# Acoustics_Board_Pg_2.net
KiCad netlist of a schematic drawn in Altium Designer
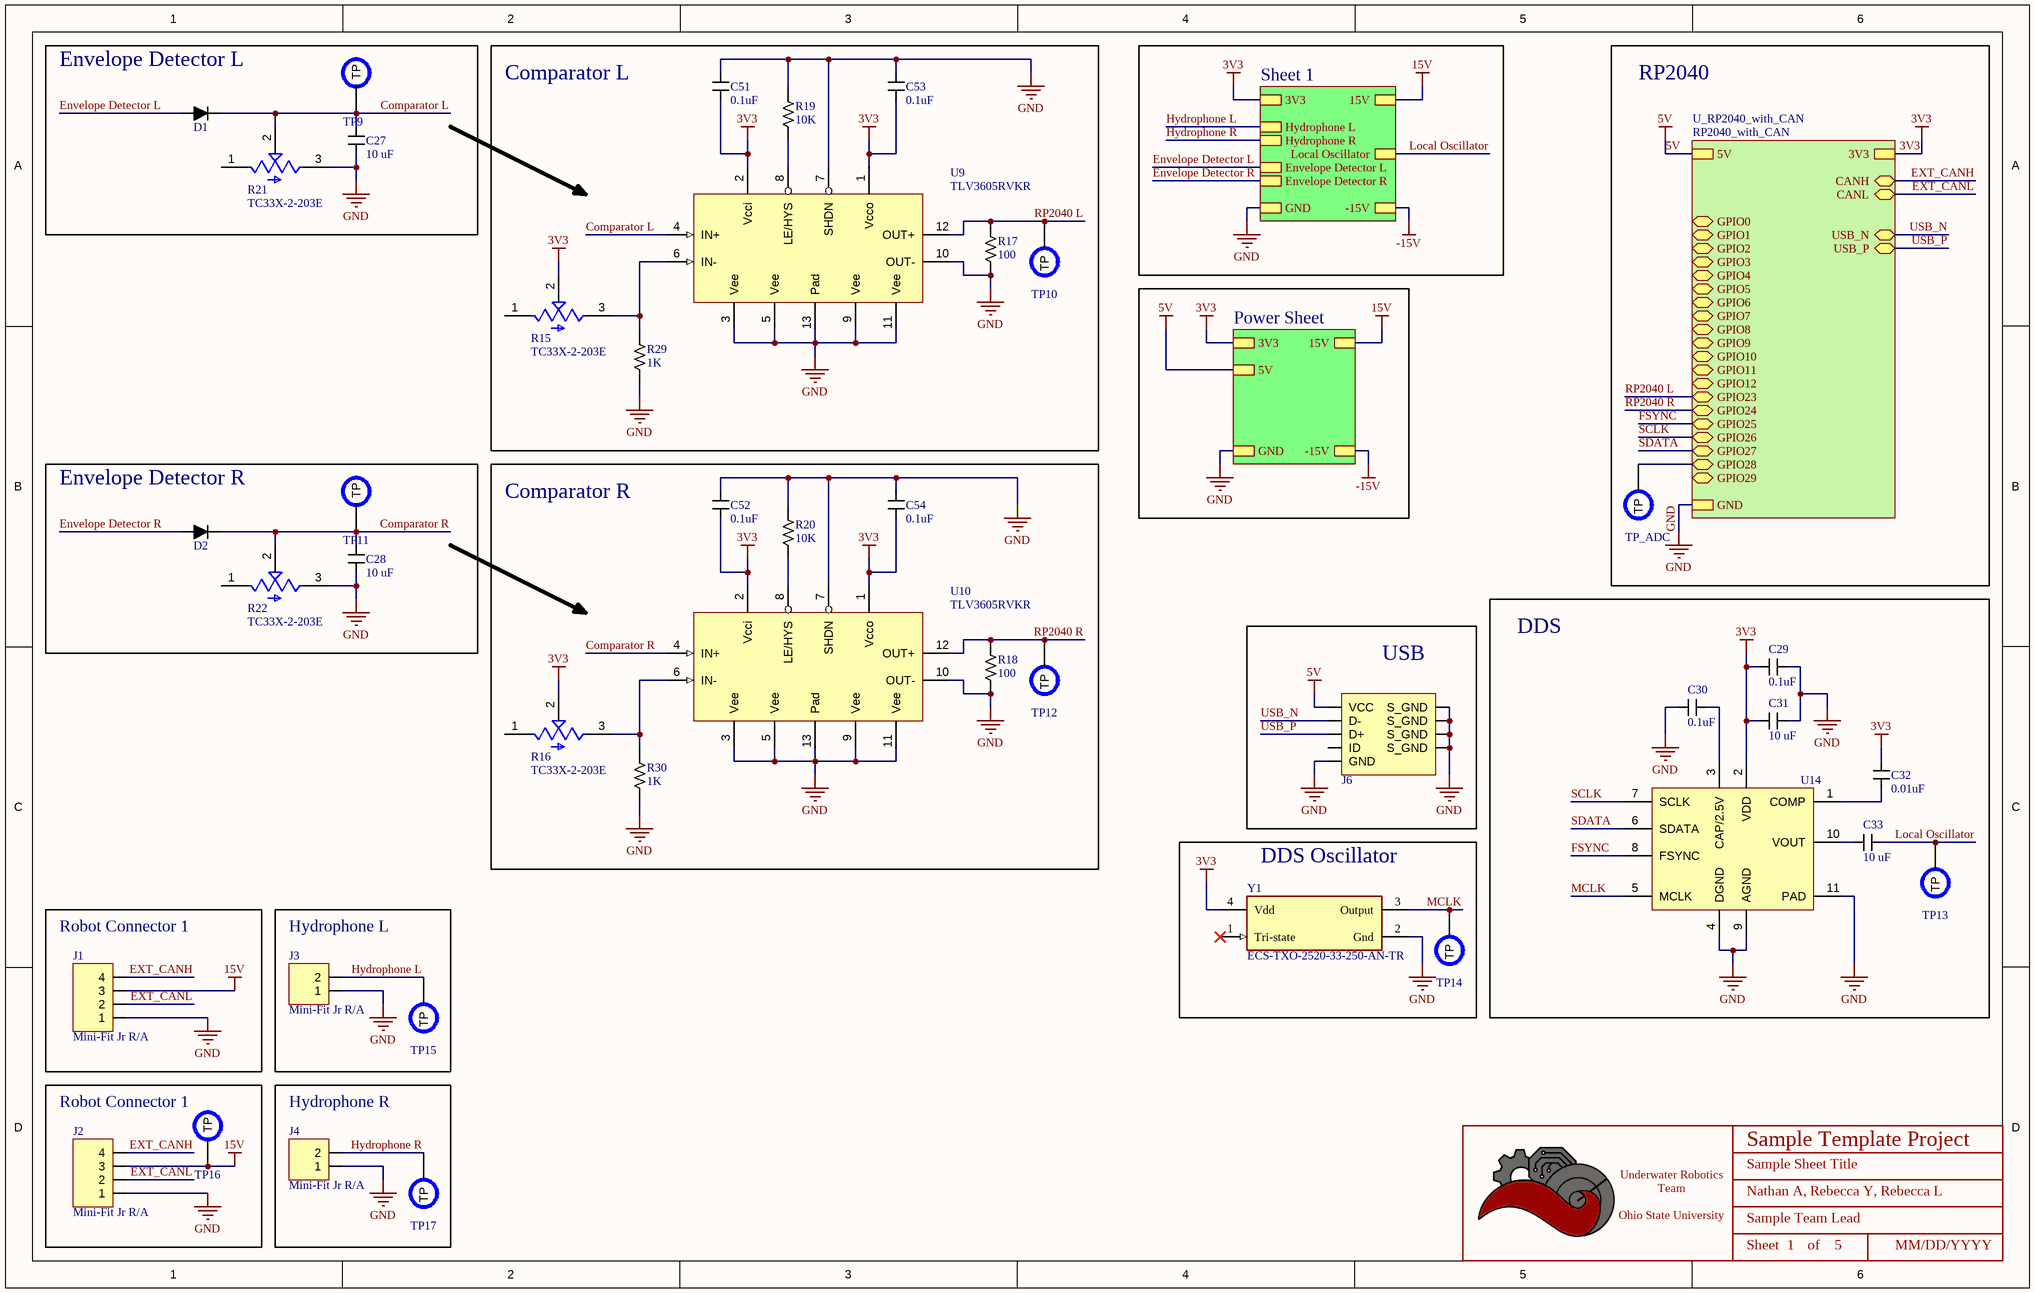
[diagram p0: Acoustics Board Pg. 2.SchDoc]

(export (version "E")
  (design (tool "Eeschema 10.0.6"))
  (components
    (comp (ref "C27")
      (value "10uF Ceramic 6.3V")
      (footprint "CAPACITOR_0603")
      (description "Cap 10uF 6.3V +/-20%\r\nCeramic 0603")
      (fields
        (field (name "TOLERANCE") "+/- 20%")
        (field (name "VOLTAGE") "6.3V")
        (field (name "VALUE (UF)") "10 uF")
        (field (name "MADE BY") "Flip B")
      )
      (libsource (lib "Capacitors") (part "CAPACITOR_10uF_0603"))
    )
    (comp (ref "C28")
      (value "10uF Ceramic 6.3V")
      (footprint "CAPACITOR_0603")
      (description "Cap 10uF 6.3V +/-20%\r\nCeramic 0603")
      (fields
        (field (name "TOLERANCE") "+/- 20%")
        (field (name "VOLTAGE") "6.3V")
        (field (name "VALUE (UF)") "10 uF")
        (field (name "MADE BY") "Flip B")
      )
      (libsource (lib "Capacitors") (part "CAPACITOR_10uF_0603"))
    )
    (comp (ref "C29")
      (value "0.1uF")
      (footprint "CAPACITOR_0603")
      (description "Cap 100nF 6.3V +/-10%\r\nCeramic 0603")
      (fields
        (field (name "TOLERANCE") "+/- 10%")
        (field (name "VOLTAGE") "6.3V")
        (field (name "MADE BY") "Flip B")
      )
      (libsource (lib "Capacitors") (part "CAPACITOR_0.1uF_0603"))
    )
    (comp (ref "C30")
      (value "0.1uF")
      (footprint "CAPACITOR_0603")
      (description "Cap 100nF 6.3V +/-10%\r\nCeramic 0603")
      (fields
        (field (name "TOLERANCE") "+/- 10%")
        (field (name "VOLTAGE") "6.3V")
        (field (name "MADE BY") "Flip B")
      )
      (libsource (lib "Capacitors") (part "CAPACITOR_0.1uF_0603"))
    )
    (comp (ref "C31")
      (value "10uF Ceramic 6.3V")
      (footprint "CAPACITOR_0603")
      (description "Cap 10uF 6.3V +/-20%\r\nCeramic 0603")
      (fields
        (field (name "TOLERANCE") "+/- 20%")
        (field (name "VOLTAGE") "6.3V")
        (field (name "VALUE (UF)") "10 uF")
        (field (name "MADE BY") "Flip B")
      )
      (libsource (lib "Capacitors") (part "CAPACITOR_10uF_0603"))
    )
    (comp (ref "C32")
      (value "0.01uF")
      (footprint "CAPACITOR_0603")
      (description "10000 pF ±10% 50V Ceramic Capacitor X7R 0603 (1608 Metric)")
      (fields
        (field (name "TOLERANCE") "+/- 10%")
        (field (name "VOLTAGE") "6.3V")
        (field (name "MADE BY") "Flip B")
      )
      (libsource (lib "Capacitors") (part "CAPACITOR_0.01uF_0603_50V"))
    )
    (comp (ref "C33")
      (value "10uF Ceramic 6.3V")
      (footprint "CAPACITOR_0603")
      (description "Cap 10uF 6.3V +/-20%\r\nCeramic 0603")
      (fields
        (field (name "TOLERANCE") "+/- 20%")
        (field (name "VOLTAGE") "6.3V")
        (field (name "VALUE (UF)") "10 uF")
        (field (name "MADE BY") "Flip B")
      )
      (libsource (lib "Capacitors") (part "CAPACITOR_10uF_0603"))
    )
    (comp (ref "C51")
      (value "0.1uF")
      (footprint "CAPACITOR_0603")
      (description "Cap 100nF 6.3V +/-10%\r\nCeramic 0603")
      (fields
        (field (name "TOLERANCE") "+/- 10%")
        (field (name "VOLTAGE") "6.3V")
        (field (name "MADE BY") "Flip B")
      )
      (libsource (lib "Capacitors") (part "CAPACITOR_0.1uF_0603"))
    )
    (comp (ref "C52")
      (value "0.1uF")
      (footprint "CAPACITOR_0603")
      (description "Cap 100nF 6.3V +/-10%\r\nCeramic 0603")
      (fields
        (field (name "TOLERANCE") "+/- 10%")
        (field (name "VOLTAGE") "6.3V")
        (field (name "MADE BY") "Flip B")
      )
      (libsource (lib "Capacitors") (part "CAPACITOR_0.1uF_0603"))
    )
    (comp (ref "C53")
      (value "0.1uF")
      (footprint "CAPACITOR_0603")
      (description "Cap 100nF 6.3V +/-10%\r\nCeramic 0603")
      (fields
        (field (name "TOLERANCE") "+/- 10%")
        (field (name "VOLTAGE") "6.3V")
        (field (name "MADE BY") "Flip B")
      )
      (libsource (lib "Capacitors") (part "CAPACITOR_0.1uF_0603"))
    )
    (comp (ref "C54")
      (value "0.1uF")
      (footprint "CAPACITOR_0603")
      (description "Cap 100nF 6.3V +/-10%\r\nCeramic 0603")
      (fields
        (field (name "TOLERANCE") "+/- 10%")
        (field (name "VOLTAGE") "6.3V")
        (field (name "MADE BY") "Flip B")
      )
      (libsource (lib "Capacitors") (part "CAPACITOR_0.1uF_0603"))
    )
    (comp (ref "D1")
      (value "BAR9002ELE6327XTMA1")
      (footprint "DIODE_0402")
      (description "RF Diode PIN - Single 80V 100 mA 250 mW PG-TSLP-2-19")
      (libsource (lib "Diodes") (part "RF Diode 80V 100mA"))
    )
    (comp (ref "D2")
      (value "BAR9002ELE6327XTMA1")
      (footprint "DIODE_0402")
      (description "RF Diode PIN - Single 80V 100 mA 250 mW PG-TSLP-2-19")
      (libsource (lib "Diodes") (part "RF Diode 80V 100mA"))
    )
    (comp (ref "J1")
      (value "Mini-Fit Jr R/A")
      (footprint "CONN_MOLEX_MINIFIT JR_4 POS_R/A")
      (description "Molex Minifit Jr. 5569 \r\n4 Pos R/A Natural")
      (fields (field (name "MANUFACTURER") "Molex") (field (name "CREATED BY") "Flip B"))
      (libsource (lib "Connectors") (part "CONN_MOLEX_MINIFIT JR_4POS_R/A"))
    )
    (comp (ref "J2")
      (value "Mini-Fit Jr R/A")
      (footprint "CONN_MOLEX_MINIFIT JR_4 POS_R/A")
      (description "Molex Minifit Jr. 5569 \r\n4 Pos R/A Natural")
      (fields (field (name "MANUFACTURER") "Molex") (field (name "CREATED BY") "Flip B"))
      (libsource (lib "Connectors") (part "CONN_MOLEX_MINIFIT JR_4POS_R/A"))
    )
    (comp (ref "J3")
      (value "Mini-Fit Jr R/A")
      (footprint "CONN_MOLEX_MINIFIT JR_2 POS_R/A")
      (description "Molex Minifit Jr. 5569 \r\n2 Pos R/A Natural")
      (fields (field (name "MANUFACTURER") "Molex") (field (name "CREATED BY") "Robert P"))
      (libsource (lib "Connectors") (part "CONN_MOLEX_MINIFIT JR_2POS_R/A"))
    )
    (comp (ref "J4")
      (value "Mini-Fit Jr R/A")
      (footprint "CONN_MOLEX_MINIFIT JR_2 POS_R/A")
      (description "Molex Minifit Jr. 5569 \r\n2 Pos R/A Natural")
      (fields (field (name "MANUFACTURER") "Molex") (field (name "CREATED BY") "Robert P"))
      (libsource (lib "Connectors") (part "CONN_MOLEX_MINIFIT JR_2POS_R/A"))
    )
    (comp (ref "J6")
      (value "USB_MICRO R/A")
      (footprint "CONN_MINIUSB")
      (description "Amphenol Micro USB-B\r\nUSB2.0 5 Pin Right Angle SMD")
      (fields (field (name "MANUFACTURER") "Amphenol") (field (name "CREATED BY") "Flip B"))
      (libsource (lib "Connectors") (part "CONN_MICROUSB"))
    )
    (comp (ref "R15")
      (value "TC33X-2-203E")
      (footprint "TRIM_TC33X-2-203E")
      (description "20 kOhms 0.1W, 1/10W J Lead Surface Mount Trimmer Potentiometer Cermet 1 Turn Top Adjustment")
      (fields (field (name "MF") "Bourns") (field (name "DIGI-KEY_PART_NUMBER") "TC33X-2-203ECT-ND"))
      (libsource (lib "Resistors") (part "TC33X-2-203E"))
    )
    (comp (ref "R16")
      (value "TC33X-2-203E")
      (footprint "TRIM_TC33X-2-203E")
      (description "20 kOhms 0.1W, 1/10W J Lead Surface Mount Trimmer Potentiometer Cermet 1 Turn Top Adjustment")
      (fields (field (name "MF") "Bourns") (field (name "DIGI-KEY_PART_NUMBER") "TC33X-2-203ECT-ND"))
      (libsource (lib "Resistors") (part "TC33X-2-203E"))
    )
    (comp (ref "R17")
      (value "100 Ohm 5% 1/8W")
      (footprint "RESISTOR_0603")
      (description "RES 100 OHM 5% 1/8W 0603")
      (fields
        (field (name "TOLERANCE") "+/- 5%")
        (field (name "VALUE  (OHMS)") "100")
        (field (name "MADE BY") "Flip B")
      )
      (libsource (lib "Resistors") (part "RESISTOR_100_0603_1"))
    )
    (comp (ref "R18")
      (value "100 Ohm 5% 1/8W")
      (footprint "RESISTOR_0603")
      (description "RES 100 OHM 5% 1/8W 0603")
      (fields
        (field (name "TOLERANCE") "+/- 5%")
        (field (name "VALUE  (OHMS)") "100")
        (field (name "MADE BY") "Flip B")
      )
      (libsource (lib "Resistors") (part "RESISTOR_100_0603_1"))
    )
    (comp (ref "R19")
      (value "10k Ohm 5% 1/10W")
      (footprint "RESISTOR_0603")
      (description "RES 10k OHM 5% 1/10W 0603")
      (fields
        (field (name "TOLERANCE") "+/- 5%")
        (field (name "VALUE  (OHMS)") "10K")
        (field (name "MADE BY") "Robert Pafford")
      )
      (libsource (lib "Resistors") (part "RESISTOR_10K_0603"))
    )
    (comp (ref "R20")
      (value "10k Ohm 5% 1/10W")
      (footprint "RESISTOR_0603")
      (description "RES 10k OHM 5% 1/10W 0603")
      (fields
        (field (name "TOLERANCE") "+/- 5%")
        (field (name "VALUE  (OHMS)") "10K")
        (field (name "MADE BY") "Robert Pafford")
      )
      (libsource (lib "Resistors") (part "RESISTOR_10K_0603"))
    )
    (comp (ref "R21")
      (value "TC33X-2-203E")
      (footprint "TRIM_TC33X-2-203E")
      (description "20 kOhms 0.1W, 1/10W J Lead Surface Mount Trimmer Potentiometer Cermet 1 Turn Top Adjustment")
      (fields (field (name "MF") "Bourns") (field (name "DIGI-KEY_PART_NUMBER") "TC33X-2-203ECT-ND"))
      (libsource (lib "Resistors") (part "TC33X-2-203E"))
    )
    (comp (ref "R22")
      (value "TC33X-2-203E")
      (footprint "TRIM_TC33X-2-203E")
      (description "20 kOhms 0.1W, 1/10W J Lead Surface Mount Trimmer Potentiometer Cermet 1 Turn Top Adjustment")
      (fields (field (name "MF") "Bourns") (field (name "DIGI-KEY_PART_NUMBER") "TC33X-2-203ECT-ND"))
      (libsource (lib "Resistors") (part "TC33X-2-203E"))
    )
    (comp (ref "R29")
      (value "1k Ohm 5% 1/10W")
      (footprint "RESISTOR_0603")
      (description "RES 1k OHM 0.5% 1/10W 0603")
      (fields
        (field (name "TOLERANCE") "+/- 0.5%")
        (field (name "VALUE  (OHMS)") "1K")
        (field (name "MADE BY") "Robert Pafford")
      )
      (libsource (lib "Resistors") (part "RESISTOR_1K_0.5%_0603"))
    )
    (comp (ref "R30")
      (value "1k Ohm 5% 1/10W")
      (footprint "RESISTOR_0603")
      (description "RES 1k OHM 0.5% 1/10W 0603")
      (fields
        (field (name "TOLERANCE") "+/- 0.5%")
        (field (name "VALUE  (OHMS)") "1K")
        (field (name "MADE BY") "Robert Pafford")
      )
      (libsource (lib "Resistors") (part "RESISTOR_1K_0.5%_0603"))
    )
    (comp (ref "TP9")
      (value "PCB Test Point")
      (footprint "TESTPOINT_1.2MM")
      (fields (field (name "MADE BY") "Robert Pafford"))
      (libsource (lib "Connectors") (part "TESTPOINT"))
    )
    (comp (ref "TP10")
      (value "PCB Test Point")
      (footprint "TESTPOINT_1.2MM")
      (fields (field (name "MADE BY") "Robert Pafford"))
      (libsource (lib "Connectors") (part "TESTPOINT"))
    )
    (comp (ref "TP11")
      (value "PCB Test Point")
      (footprint "TESTPOINT_1.2MM")
      (fields (field (name "MADE BY") "Robert Pafford"))
      (libsource (lib "Connectors") (part "TESTPOINT"))
    )
    (comp (ref "TP12")
      (value "PCB Test Point")
      (footprint "TESTPOINT_1.2MM")
      (fields (field (name "MADE BY") "Robert Pafford"))
      (libsource (lib "Connectors") (part "TESTPOINT"))
    )
    (comp (ref "TP13")
      (value "PCB Test Point")
      (footprint "TESTPOINT_1.2MM")
      (fields (field (name "MADE BY") "Robert Pafford"))
      (libsource (lib "Connectors") (part "TESTPOINT"))
    )
    (comp (ref "TP14")
      (value "PCB Test Point")
      (footprint "TESTPOINT_1.2MM")
      (fields (field (name "MADE BY") "Robert Pafford"))
      (libsource (lib "Connectors") (part "TESTPOINT"))
    )
    (comp (ref "TP15")
      (value "PCB Test Point")
      (footprint "TESTPOINT_1.2MM")
      (fields (field (name "MADE BY") "Robert Pafford"))
      (libsource (lib "Connectors") (part "TESTPOINT"))
    )
    (comp (ref "TP16")
      (value "PCB Test Point")
      (footprint "TESTPOINT_1.2MM")
      (fields (field (name "MADE BY") "Robert Pafford"))
      (libsource (lib "Connectors") (part "TESTPOINT"))
    )
    (comp (ref "TP17")
      (value "PCB Test Point")
      (footprint "TESTPOINT_1.2MM")
      (fields (field (name "MADE BY") "Robert Pafford"))
      (libsource (lib "Connectors") (part "TESTPOINT"))
    )
    (comp (ref "TP_ADC")
      (value "PCB Test Point")
      (footprint "TESTPOINT_1.2MM")
      (fields (field (name "MADE BY") "Robert Pafford"))
      (libsource (lib "Connectors") (part "TESTPOINT"))
    )
    (comp (ref "U9")
      (value "TLV3605RVKR")
      (footprint "TLV3605RVKR")
      (description "IC COMPARATOR 1 GEN PUR 12WQFN")
      (fields (field (name "MANUFACTURER") "Texas Instruments") (field (name "CREATED BY") "Nathan Ayer"))
      (libsource (lib "Integrated Circuits") (part "TLV3605RVKR"))
    )
    (comp (ref "U10")
      (value "TLV3605RVKR")
      (footprint "TLV3605RVKR")
      (description "IC COMPARATOR 1 GEN PUR 12WQFN")
      (fields (field (name "MANUFACTURER") "Texas Instruments") (field (name "CREATED BY") "Nathan Ayer"))
      (libsource (lib "Integrated Circuits") (part "TLV3605RVKR"))
    )
    (comp (ref "U14")
      (value "IC DDS 5MHZ 10BIT 10LFCSP")
      (footprint "CP-10-9")
      (description "Direct Digital Synthesis IC 10 b 5 MHz 28 b Tuning 10-LFCSP-WD (3x3)")
      (libsource (lib "Integrated Circuits") (part "AD9837ACPZ"))
    )
    (comp (ref "Y1")
      (value "ECS-TXO-2520-33-250-AN-TR")
      (footprint "FP-ECS-TXO-2520-MFG")
      (description "XTAL OSC TCXO 25.0000MHZ HCMOS")
      (libsource (lib "Altium Content Vault") (part "04cd953f3cf158082f8c09fbdb924ef"))
    )
  )
  (nets
    (net (code "2") (name "/Comparator L") (class "Default")
      (node (ref "C27") (pin "1") (pinfunction "1_1") (pintype "passive"))
      (node (ref "D1") (pin "2") (pinfunction "2_2") (pintype "passive"))
      (node (ref "R21") (pin "2") (pinfunction "W_2") (pintype "passive"))
      (node (ref "TP9") (pin "TP") (pinfunction "TP_TP") (pintype "passive"))
      (node (ref "U9") (pin "4") (pinfunction "IN+_4") (pintype "input"))
    )
    (net (code "3") (name "/Comparator R") (class "Default")
      (node (ref "C28") (pin "1") (pinfunction "1_1") (pintype "passive"))
      (node (ref "D2") (pin "2") (pinfunction "2_2") (pintype "passive"))
      (node (ref "R22") (pin "2") (pinfunction "W_2") (pintype "passive"))
      (node (ref "TP11") (pin "TP") (pinfunction "TP_TP") (pintype "passive"))
      (node (ref "U10") (pin "4") (pinfunction "IN+_4") (pintype "input"))
    )
    (net (code "4") (name "/EXT_CANH") (class "Default")
      (node (ref "J1") (pin "4") (pinfunction "4_4") (pintype "passive"))
      (node (ref "J2") (pin "4") (pinfunction "4_4") (pintype "passive"))
    )
    (net (code "5") (name "/EXT_CANL") (class "Default")
      (node (ref "J1") (pin "2") (pinfunction "2_2") (pintype "passive"))
      (node (ref "J2") (pin "2") (pinfunction "2_2") (pintype "passive"))
    )
    (net (code "6") (name "/Envelope Detector L") (class "Default")
      (node (ref "D1") (pin "1") (pinfunction "1_1") (pintype "passive"))
    )
    (net (code "7") (name "/Envelope Detector R") (class "Default")
      (node (ref "D2") (pin "1") (pinfunction "1_1") (pintype "passive"))
    )
    (net (code "8") (name "/FSYNC") (class "Default")
      (node (ref "U14") (pin "8") (pinfunction "FSYNC_8") (pintype "passive"))
    )
    (net (code "22") (name "/GPIO28") (class "Default")
      (node (ref "TP_ADC") (pin "TP") (pinfunction "TP_TP") (pintype "passive"))
    )
    (net (code "24") (name "/Hydrophone L") (class "Default")
      (node (ref "J3") (pin "2") (pinfunction "2_2") (pintype "passive"))
      (node (ref "TP15") (pin "TP") (pinfunction "TP_TP") (pintype "passive"))
    )
    (net (code "25") (name "/Hydrophone R") (class "Default")
      (node (ref "J4") (pin "2") (pinfunction "2_2") (pintype "passive"))
      (node (ref "TP17") (pin "TP") (pinfunction "TP_TP") (pintype "passive"))
    )
    (net (code "26") (name "/Local Oscillator") (class "Default")
      (node (ref "C33") (pin "2") (pinfunction "2_2") (pintype "passive"))
      (node (ref "TP13") (pin "TP") (pinfunction "TP_TP") (pintype "passive"))
    )
    (net (code "27") (name "/MCLK") (class "Default")
      (node (ref "TP14") (pin "TP") (pinfunction "TP_TP") (pintype "passive"))
      (node (ref "U14") (pin "5") (pinfunction "MCLK_5") (pintype "passive"))
      (node (ref "Y1") (pin "3") (pinfunction "Output_3") (pintype "tri_state"))
    )
    (net (code "28") (name "/RP2040 L") (class "Default")
      (node (ref "R17") (pin "1") (pinfunction "1_1") (pintype "passive"))
      (node (ref "TP10") (pin "TP") (pinfunction "TP_TP") (pintype "passive"))
      (node (ref "U9") (pin "12") (pinfunction "OUT+_12") (pintype "passive"))
    )
    (net (code "29") (name "/RP2040 R") (class "Default")
      (node (ref "R18") (pin "1") (pinfunction "1_1") (pintype "passive"))
      (node (ref "TP12") (pin "TP") (pinfunction "TP_TP") (pintype "passive"))
      (node (ref "U10") (pin "12") (pinfunction "OUT+_12") (pintype "passive"))
    )
    (net (code "30") (name "/SCLK") (class "Default")
      (node (ref "U14") (pin "7") (pinfunction "SCLK_7") (pintype "passive"))
    )
    (net (code "31") (name "/SDATA") (class "Default")
      (node (ref "U14") (pin "6") (pinfunction "SDATA_6") (pintype "passive"))
    )
    (net (code "32") (name "/USB_N") (class "Default")
      (node (ref "J6") (pin "2") (pinfunction "D-_2") (pintype "passive"))
    )
    (net (code "33") (name "/USB_P") (class "Default")
      (node (ref "J6") (pin "3") (pinfunction "D+_3") (pintype "passive"))
    )
    (net (code "34") (name "3V3") (class "Default")
      (node (ref "C29") (pin "2") (pinfunction "2_2") (pintype "passive"))
      (node (ref "C31") (pin "1") (pinfunction "1_1") (pintype "passive"))
      (node (ref "C32") (pin "1") (pinfunction "1_1") (pintype "passive"))
      (node (ref "C51") (pin "1") (pinfunction "1_1") (pintype "passive"))
      (node (ref "C52") (pin "1") (pinfunction "1_1") (pintype "passive"))
      (node (ref "C53") (pin "1") (pinfunction "1_1") (pintype "passive"))
      (node (ref "C54") (pin "1") (pinfunction "1_1") (pintype "passive"))
      (node (ref "R15") (pin "2") (pinfunction "W_2") (pintype "passive"))
      (node (ref "R16") (pin "2") (pinfunction "W_2") (pintype "passive"))
      (node (ref "U10") (pin "1") (pinfunction "Vcco_1") (pintype "power_in"))
      (node (ref "U10") (pin "2") (pinfunction "Vcci_2") (pintype "power_in"))
      (node (ref "U14") (pin "2") (pinfunction "VDD_2") (pintype "passive"))
      (node (ref "U9") (pin "1") (pinfunction "Vcco_1") (pintype "power_in"))
      (node (ref "U9") (pin "2") (pinfunction "Vcci_2") (pintype "power_in"))
      (node (ref "Y1") (pin "4") (pinfunction "Vdd_4") (pintype "power_in"))
    )
    (net (code "35") (name "5V") (class "Default")
      (node (ref "J6") (pin "1") (pinfunction "VCC_1") (pintype "passive"))
    )
    (net (code "36") (name "15V") (class "Default")
      (node (ref "J1") (pin "3") (pinfunction "3_3") (pintype "passive"))
      (node (ref "J2") (pin "3") (pinfunction "3_3") (pintype "passive"))
      (node (ref "TP16") (pin "TP") (pinfunction "TP_TP") (pintype "passive"))
    )
    (net (code "37") (name "GND") (class "Default")
      (node (ref "C27") (pin "2") (pinfunction "2_2") (pintype "passive"))
      (node (ref "C28") (pin "2") (pinfunction "2_2") (pintype "passive"))
      (node (ref "C29") (pin "1") (pinfunction "1_1") (pintype "passive"))
      (node (ref "C30") (pin "1") (pinfunction "1_1") (pintype "passive"))
      (node (ref "C31") (pin "2") (pinfunction "2_2") (pintype "passive"))
      (node (ref "C51") (pin "2") (pinfunction "2_2") (pintype "passive"))
      (node (ref "C52") (pin "2") (pinfunction "2_2") (pintype "passive"))
      (node (ref "C53") (pin "2") (pinfunction "2_2") (pintype "passive"))
      (node (ref "C54") (pin "2") (pinfunction "2_2") (pintype "passive"))
      (node (ref "J1") (pin "1") (pinfunction "1_1") (pintype "passive"))
      (node (ref "J2") (pin "1") (pinfunction "1_1") (pintype "passive"))
      (node (ref "J3") (pin "1") (pinfunction "1_1") (pintype "passive"))
      (node (ref "J4") (pin "1") (pinfunction "1_1") (pintype "passive"))
      (node (ref "J6") (pin "5") (pinfunction "GND_5") (pintype "passive"))
      (node (ref "J6") (pin "6") (pinfunction "S_GND_6") (pintype "passive"))
      (node (ref "J6") (pin "7") (pinfunction "S_GND_7") (pintype "passive"))
      (node (ref "J6") (pin "8") (pinfunction "S_GND_8") (pintype "passive"))
      (node (ref "J6") (pin "9") (pinfunction "S_GND_9") (pintype "passive"))
      (node (ref "R17") (pin "2") (pinfunction "2_2") (pintype "passive"))
      (node (ref "R18") (pin "2") (pinfunction "2_2") (pintype "passive"))
      (node (ref "R19") (pin "1") (pinfunction "1_1") (pintype "passive"))
      (node (ref "R20") (pin "1") (pinfunction "1_1") (pintype "passive"))
      (node (ref "R21") (pin "3") (pinfunction "CW_3") (pintype "passive"))
      (node (ref "R22") (pin "3") (pinfunction "CW_3") (pintype "passive"))
      (node (ref "R29") (pin "2") (pinfunction "2_2") (pintype "passive"))
      (node (ref "R30") (pin "2") (pinfunction "2_2") (pintype "passive"))
      (node (ref "U10") (pin "10") (pinfunction "OUT-_10") (pintype "passive"))
      (node (ref "U10") (pin "11") (pinfunction "Vee_11") (pintype "power_in"))
      (node (ref "U10") (pin "13") (pinfunction "Pad_13") (pintype "power_in"))
      (node (ref "U10") (pin "3") (pinfunction "Vee_3") (pintype "power_in"))
      (node (ref "U10") (pin "5") (pinfunction "Vee_5") (pintype "power_in"))
      (node (ref "U10") (pin "7") (pinfunction "SHDN_7") (pintype "passive"))
      (node (ref "U10") (pin "9") (pinfunction "Vee_9") (pintype "power_in"))
      (node (ref "U14") (pin "11") (pinfunction "PAD_11") (pintype "passive"))
      (node (ref "U14") (pin "4") (pinfunction "DGND_4") (pintype "passive"))
      (node (ref "U14") (pin "9") (pinfunction "AGND_9") (pintype "passive"))
      (node (ref "U9") (pin "10") (pinfunction "OUT-_10") (pintype "passive"))
      (node (ref "U9") (pin "11") (pinfunction "Vee_11") (pintype "power_in"))
      (node (ref "U9") (pin "13") (pinfunction "Pad_13") (pintype "power_in"))
      (node (ref "U9") (pin "3") (pinfunction "Vee_3") (pintype "power_in"))
      (node (ref "U9") (pin "5") (pinfunction "Vee_5") (pintype "power_in"))
      (node (ref "U9") (pin "7") (pinfunction "SHDN_7") (pintype "passive"))
      (node (ref "U9") (pin "9") (pinfunction "Vee_9") (pintype "power_in"))
      (node (ref "Y1") (pin "2") (pinfunction "Gnd_2") (pintype "power_in"))
    )
    (net (code "38") (name "Net-(R15-CW)") (class "Default")
      (node (ref "R15") (pin "3") (pinfunction "CW_3") (pintype "passive"))
      (node (ref "R29") (pin "1") (pinfunction "1_1") (pintype "passive"))
      (node (ref "U9") (pin "6") (pinfunction "IN-_6") (pintype "input"))
    )
    (net (code "39") (name "Net-(R16-CW)") (class "Default")
      (node (ref "R16") (pin "3") (pinfunction "CW_3") (pintype "passive"))
      (node (ref "R30") (pin "1") (pinfunction "1_1") (pintype "passive"))
      (node (ref "U10") (pin "6") (pinfunction "IN-_6") (pintype "input"))
    )
    (net (code "40") (name "Net-(U9-LE{slash}HYS)") (class "Default")
      (node (ref "R19") (pin "2") (pinfunction "2_2") (pintype "passive"))
      (node (ref "U9") (pin "8") (pinfunction "LE/HYS_8") (pintype "passive"))
    )
    (net (code "41") (name "Net-(U10-LE{slash}HYS)") (class "Default")
      (node (ref "R20") (pin "2") (pinfunction "2_2") (pintype "passive"))
      (node (ref "U10") (pin "8") (pinfunction "LE/HYS_8") (pintype "passive"))
    )
    (net (code "42") (name "Net-(U14-CAP{slash}2.5V)") (class "Default")
      (node (ref "C30") (pin "2") (pinfunction "2_2") (pintype "passive"))
      (node (ref "U14") (pin "3") (pinfunction "CAP/2.5V_3") (pintype "passive"))
    )
    (net (code "43") (name "Net-(U14-COMP)") (class "Default")
      (node (ref "C32") (pin "2") (pinfunction "2_2") (pintype "passive"))
      (node (ref "U14") (pin "1") (pinfunction "COMP_1") (pintype "passive"))
    )
    (net (code "44") (name "Net-(U14-VOUT)") (class "Default")
      (node (ref "C33") (pin "1") (pinfunction "1_1") (pintype "passive"))
      (node (ref "U14") (pin "10") (pinfunction "VOUT_10") (pintype "passive"))
    )
    (net (code "45") (name "unconnected-(J6-ID-Pad4)") (class "Default")
      (node (ref "J6") (pin "4") (pinfunction "ID_4") (pintype "passive"))
    )
    (net (code "46") (name "unconnected-(R15-CCW-Pad1)") (class "Default")
      (node (ref "R15") (pin "1") (pinfunction "CCW_1") (pintype "passive"))
    )
    (net (code "47") (name "unconnected-(R16-CCW-Pad1)") (class "Default")
      (node (ref "R16") (pin "1") (pinfunction "CCW_1") (pintype "passive"))
    )
    (net (code "48") (name "unconnected-(R21-CCW-Pad1)") (class "Default")
      (node (ref "R21") (pin "1") (pinfunction "CCW_1") (pintype "passive"))
    )
    (net (code "49") (name "unconnected-(R22-CCW-Pad1)") (class "Default")
      (node (ref "R22") (pin "1") (pinfunction "CCW_1") (pintype "passive"))
    )
    (net (code "50") (name "unconnected-(Y1-Tri-state-Pad1)") (class "Default")
      (node (ref "Y1") (pin "1") (pinfunction "Tri-state_1") (pintype "input+no_connect"))
    )
  )
)
